# H-Bridge.net
KiCad netlist of a schematic drawn in Altium Designer
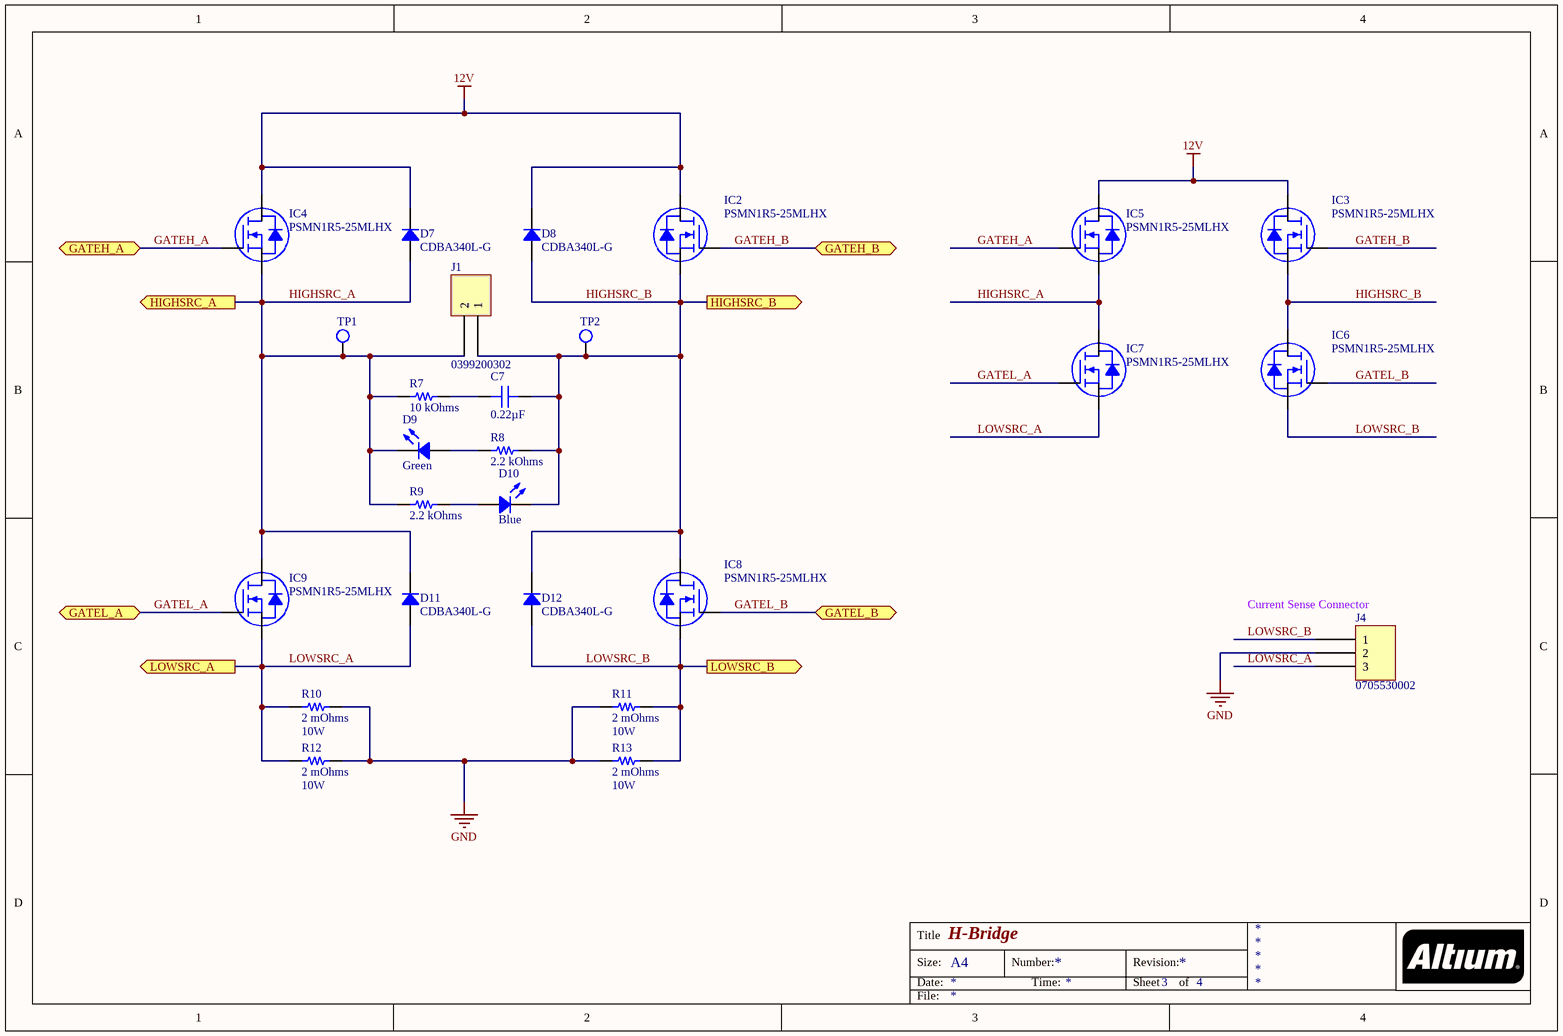
[diagram p0: H-Bridge.SchDoc]

(export (version "E")
  (design (tool "Eeschema 10.0.6"))
  (components
    (comp (ref "C7")
      (value "0.22µF")
      (footprint "CAP 0805_2012")
      (description "CAP CER 0.22UF 50V X7R 0805")
      (fields (field (name "PART NUMBER") "08055C224KAZ2A") (field (name "MANUFACTURER") "AVX Corporation"))
      (libsource (lib "altiumlibrary.com") (part "Capacitor"))
    )
    (comp (ref "D7")
      (value "CDBA340L-G")
      (footprint "DO214AC SMA")
      (description "DIODE SCHOTTKY 40V 3A DO214AC")
      (fields (field (name "MANUFACTURER") "Comchip Technology"))
      (libsource (lib "altiumlibrary.com") (part "Diode"))
    )
    (comp (ref "D8")
      (value "CDBA340L-G")
      (footprint "DO214AC SMA")
      (description "DIODE SCHOTTKY 40V 3A DO214AC")
      (fields (field (name "MANUFACTURER") "Comchip Technology"))
      (libsource (lib "altiumlibrary.com") (part "Diode"))
    )
    (comp (ref "D9")
      (value "Green")
      (footprint "LED 0603_1608 GREEN")
      (description "LED GREEN CLEAR CHIP SMD")
      (fields (field (name "PART NUMBER") "XZMG53W-1") (field (name "MANUFACTURER") "SunLED"))
      (libsource (lib "altiumlibrary.com") (part "LED"))
    )
    (comp (ref "D10")
      (value "Blue")
      (footprint "LED 0603_1608 BLUE")
      (description "LED BLUE CLEAR 2SMD")
      (fields
        (field (name "PART NUMBER") "19-213SUBC/S400-A5/S208-2/TR8")
        (field (name "MANUFACTURER") "Everlight Electronics Co Ltd")
      )
      (libsource (lib "altiumlibrary.com") (part "LED"))
    )
    (comp (ref "D11")
      (value "CDBA340L-G")
      (footprint "DO214AC SMA")
      (description "DIODE SCHOTTKY 40V 3A DO214AC")
      (fields (field (name "MANUFACTURER") "Comchip Technology"))
      (libsource (lib "altiumlibrary.com") (part "Diode"))
    )
    (comp (ref "D12")
      (value "CDBA340L-G")
      (footprint "DO214AC SMA")
      (description "DIODE SCHOTTKY 40V 3A DO214AC")
      (fields (field (name "MANUFACTURER") "Comchip Technology"))
      (libsource (lib "altiumlibrary.com") (part "Diode"))
    )
    (comp (ref "IC2")
      (value "PSMN1R5-25MLHX")
      (footprint "NEXPERIA LFPAK33 SOT1210")
      (description "MOSFET N-CH 25V 150A LFPAK33")
      (fields (field (name "MANUFACTURER") "Nexperia USA Inc."))
      (libsource (lib "") (part "MOSFET SINGLE GDS_1"))
    )
    (comp (ref "IC3")
      (value "PSMN1R5-25MLHX")
      (footprint "NEXPERIA LFPAK33 SOT1210")
      (description "MOSFET N-CH 25V 150A LFPAK33")
      (fields (field (name "MANUFACTURER") "Nexperia USA Inc."))
      (libsource (lib "") (part "MOSFET SINGLE GDS_1"))
    )
    (comp (ref "IC4")
      (value "PSMN1R5-25MLHX")
      (footprint "NEXPERIA LFPAK33 SOT1210")
      (description "MOSFET N-CH 25V 150A LFPAK33")
      (fields (field (name "MANUFACTURER") "Nexperia USA Inc."))
      (libsource (lib "altiumlibrary.com") (part "MOSFET SINGLE GDS"))
    )
    (comp (ref "IC5")
      (value "PSMN1R5-25MLHX")
      (footprint "NEXPERIA LFPAK33 SOT1210")
      (description "MOSFET N-CH 25V 150A LFPAK33")
      (fields (field (name "MANUFACTURER") "Nexperia USA Inc."))
      (libsource (lib "altiumlibrary.com") (part "MOSFET SINGLE GDS"))
    )
    (comp (ref "IC6")
      (value "PSMN1R5-25MLHX")
      (footprint "NEXPERIA LFPAK33 SOT1210")
      (description "MOSFET N-CH 25V 150A LFPAK33")
      (fields (field (name "MANUFACTURER") "Nexperia USA Inc."))
      (libsource (lib "") (part "MOSFET SINGLE GDS_1"))
    )
    (comp (ref "IC7")
      (value "PSMN1R5-25MLHX")
      (footprint "NEXPERIA LFPAK33 SOT1210")
      (description "MOSFET N-CH 25V 150A LFPAK33")
      (fields (field (name "MANUFACTURER") "Nexperia USA Inc."))
      (libsource (lib "altiumlibrary.com") (part "MOSFET SINGLE GDS"))
    )
    (comp (ref "IC8")
      (value "PSMN1R5-25MLHX")
      (footprint "NEXPERIA LFPAK33 SOT1210")
      (description "MOSFET N-CH 25V 150A LFPAK33")
      (fields (field (name "MANUFACTURER") "Nexperia USA Inc."))
      (libsource (lib "") (part "MOSFET SINGLE GDS_1"))
    )
    (comp (ref "IC9")
      (value "PSMN1R5-25MLHX")
      (footprint "NEXPERIA LFPAK33 SOT1210")
      (description "MOSFET N-CH 25V 150A LFPAK33")
      (fields (field (name "MANUFACTURER") "Nexperia USA Inc."))
      (libsource (lib "altiumlibrary.com") (part "MOSFET SINGLE GDS"))
    )
    (comp (ref "J1")
      (value "0399200302")
      (footprint "MOLEX 0399200302")
      (description "TERM BLK 2P SIDE ENTRY 15MM PCB")
      (fields (field (name "MANUFACTURER") "Molex") (field (name "VOLTAGE") "600 V"))
      (libsource (lib "altiumlibrary.com") (part "2 Pin"))
    )
    (comp (ref "J4")
      (value "0705530002")
      (footprint "MOLEX SDA-70553-3PIN")
      (description "CONN HEADER R/A 3POS 2.54MM")
      (fields (field (name "MANUFACTURER") "Molex"))
      (libsource (lib "altiumlibrary.com") (part "3 Pin"))
    )
    (comp (ref "R7")
      (value "10 kOhms")
      (footprint "RES 0805_2012")
      (description "RES SMD 10K OHM 5% 1/2W 0805")
      (fields
        (field (name "PART NUMBER") "ERJ-P06J103V")
        (field (name "MANUFACTURER") "Panasonic Electronic Components")
      )
      (libsource (lib "altiumlibrary.com") (part "Resistor"))
    )
    (comp (ref "R8")
      (value "2.2 kOhms")
      (footprint "RES 0603_1608")
      (description "RES SMD 2.2K OHM 5% 1/4W 0603")
      (fields
        (field (name "PART NUMBER") "ERJ-PA3J222V")
        (field (name "MANUFACTURER") "Panasonic Electronic Components")
      )
      (libsource (lib "altiumlibrary.com") (part "Resistor"))
    )
    (comp (ref "R9")
      (value "2.2 kOhms")
      (footprint "RES 0603_1608")
      (description "RES SMD 2.2K OHM 5% 1/4W 0603")
      (fields
        (field (name "PART NUMBER") "ERJ-PA3J222V")
        (field (name "MANUFACTURER") "Panasonic Electronic Components")
      )
      (libsource (lib "altiumlibrary.com") (part "Resistor"))
    )
    (comp (ref "R10")
      (value "2 mOhms")
      (footprint "VISHAY WSHP2818")
      (description "RES 0.002 OHM 1% 10W 2818")
      (fields
        (field (name "PART NUMBER") "WSHP28182L000FEA")
        (field (name "MANUFACTURER") "Vishay Dale")
        (field (name "POWER (WATTS)") "10W")
      )
      (libsource (lib "altiumlibrary.com") (part "Resistor"))
    )
    (comp (ref "R11")
      (value "2 mOhms")
      (footprint "VISHAY WSHP2818")
      (description "RES 0.002 OHM 1% 10W 2818")
      (fields
        (field (name "PART NUMBER") "WSHP28182L000FEA")
        (field (name "MANUFACTURER") "Vishay Dale")
        (field (name "POWER (WATTS)") "10W")
      )
      (libsource (lib "altiumlibrary.com") (part "Resistor"))
    )
    (comp (ref "R12")
      (value "2 mOhms")
      (footprint "VISHAY WSHP2818")
      (description "RES 0.002 OHM 1% 10W 2818")
      (fields
        (field (name "PART NUMBER") "WSHP28182L000FEA")
        (field (name "MANUFACTURER") "Vishay Dale")
        (field (name "POWER (WATTS)") "10W")
      )
      (libsource (lib "altiumlibrary.com") (part "Resistor"))
    )
    (comp (ref "R13")
      (value "2 mOhms")
      (footprint "VISHAY WSHP2818")
      (description "RES 0.002 OHM 1% 10W 2818")
      (fields
        (field (name "PART NUMBER") "WSHP28182L000FEA")
        (field (name "MANUFACTURER") "Vishay Dale")
        (field (name "POWER (WATTS)") "10W")
      )
      (libsource (lib "altiumlibrary.com") (part "Resistor"))
    )
    (comp (ref "TP1")
      (value "Test Point")
      (footprint "TestPoint-1.5mm")
      (libsource (lib "CelestialUseful") (part "Test Point"))
    )
    (comp (ref "TP2")
      (value "Test Point")
      (footprint "TestPoint-1.5mm")
      (libsource (lib "CelestialUseful") (part "Test Point"))
    )
  )
  (nets
    (net (code "1") (name "/GATEH_A") (class "Default")
      (node (ref "IC4") (pin "G") (pinfunction "G_G") (pintype "passive"))
      (node (ref "IC5") (pin "G") (pinfunction "G_G") (pintype "passive"))
    )
    (net (code "2") (name "/GATEH_B") (class "Default")
      (node (ref "IC2") (pin "G") (pinfunction "G_G") (pintype "passive"))
      (node (ref "IC3") (pin "G") (pinfunction "G_G") (pintype "passive"))
    )
    (net (code "3") (name "/GATEL_A") (class "Default")
      (node (ref "IC7") (pin "G") (pinfunction "G_G") (pintype "passive"))
      (node (ref "IC9") (pin "G") (pinfunction "G_G") (pintype "passive"))
    )
    (net (code "4") (name "/GATEL_B") (class "Default")
      (node (ref "IC6") (pin "G") (pinfunction "G_G") (pintype "passive"))
      (node (ref "IC8") (pin "G") (pinfunction "G_G") (pintype "passive"))
    )
    (net (code "5") (name "/HIGHSRC_A") (class "Default")
      (node (ref "D11") (pin "2") (pinfunction "2_2") (pintype "passive"))
      (node (ref "D7") (pin "1") (pinfunction "1_1") (pintype "passive"))
      (node (ref "D9") (pin "2") (pinfunction "2_2") (pintype "passive"))
      (node (ref "IC4") (pin "S") (pinfunction "S_S") (pintype "passive"))
      (node (ref "IC5") (pin "S") (pinfunction "S_S") (pintype "passive"))
      (node (ref "IC7") (pin "D") (pinfunction "D_D") (pintype "passive"))
      (node (ref "IC9") (pin "D") (pinfunction "D_D") (pintype "passive"))
      (node (ref "J1") (pin "2") (pinfunction "2_2") (pintype "passive"))
      (node (ref "R7") (pin "1") (pinfunction "1_1") (pintype "passive"))
      (node (ref "R9") (pin "1") (pinfunction "1_1") (pintype "passive"))
      (node (ref "TP1") (pin "1") (pinfunction "TP_1") (pintype "passive"))
    )
    (net (code "6") (name "/HIGHSRC_B") (class "Default")
      (node (ref "C7") (pin "2") (pinfunction "2_2") (pintype "passive"))
      (node (ref "D10") (pin "2") (pinfunction "2_2") (pintype "passive"))
      (node (ref "D12") (pin "2") (pinfunction "2_2") (pintype "passive"))
      (node (ref "D8") (pin "1") (pinfunction "1_1") (pintype "passive"))
      (node (ref "IC2") (pin "S") (pinfunction "S_S") (pintype "passive"))
      (node (ref "IC3") (pin "S") (pinfunction "S_S") (pintype "passive"))
      (node (ref "IC6") (pin "D") (pinfunction "D_D") (pintype "passive"))
      (node (ref "IC8") (pin "D") (pinfunction "D_D") (pintype "passive"))
      (node (ref "J1") (pin "1") (pinfunction "1_1") (pintype "passive"))
      (node (ref "R8") (pin "2") (pinfunction "2_2") (pintype "passive"))
      (node (ref "TP2") (pin "1") (pinfunction "TP_1") (pintype "passive"))
    )
    (net (code "7") (name "/LOWSRC_A") (class "Default")
      (node (ref "D11") (pin "1") (pinfunction "1_1") (pintype "passive"))
      (node (ref "IC7") (pin "S") (pinfunction "S_S") (pintype "passive"))
      (node (ref "IC9") (pin "S") (pinfunction "S_S") (pintype "passive"))
      (node (ref "J4") (pin "3") (pinfunction "3_3") (pintype "passive"))
      (node (ref "R10") (pin "1") (pinfunction "1_1") (pintype "passive"))
      (node (ref "R12") (pin "1") (pinfunction "1_1") (pintype "passive"))
    )
    (net (code "8") (name "/LOWSRC_B") (class "Default")
      (node (ref "D12") (pin "1") (pinfunction "1_1") (pintype "passive"))
      (node (ref "IC6") (pin "S") (pinfunction "S_S") (pintype "passive"))
      (node (ref "IC8") (pin "S") (pinfunction "S_S") (pintype "passive"))
      (node (ref "J4") (pin "1") (pinfunction "1_1") (pintype "passive"))
      (node (ref "R11") (pin "2") (pinfunction "2_2") (pintype "passive"))
      (node (ref "R13") (pin "2") (pinfunction "2_2") (pintype "passive"))
    )
    (net (code "9") (name "12V") (class "Default")
      (node (ref "D7") (pin "2") (pinfunction "2_2") (pintype "passive"))
      (node (ref "D8") (pin "2") (pinfunction "2_2") (pintype "passive"))
      (node (ref "IC2") (pin "D") (pinfunction "D_D") (pintype "passive"))
      (node (ref "IC3") (pin "D") (pinfunction "D_D") (pintype "passive"))
      (node (ref "IC4") (pin "D") (pinfunction "D_D") (pintype "passive"))
      (node (ref "IC5") (pin "D") (pinfunction "D_D") (pintype "passive"))
    )
    (net (code "10") (name "GND") (class "Default")
      (node (ref "J4") (pin "2") (pinfunction "2_2") (pintype "passive"))
      (node (ref "R10") (pin "2") (pinfunction "2_2") (pintype "passive"))
      (node (ref "R11") (pin "1") (pinfunction "1_1") (pintype "passive"))
      (node (ref "R12") (pin "2") (pinfunction "2_2") (pintype "passive"))
      (node (ref "R13") (pin "1") (pinfunction "1_1") (pintype "passive"))
    )
    (net (code "11") (name "Net-(C7-Pad1)") (class "Default")
      (node (ref "C7") (pin "1") (pinfunction "1_1") (pintype "passive"))
      (node (ref "R7") (pin "2") (pinfunction "2_2") (pintype "passive"))
    )
    (net (code "12") (name "Net-(D9-Pad1)") (class "Default")
      (node (ref "D9") (pin "1") (pinfunction "1_1") (pintype "passive"))
      (node (ref "R8") (pin "1") (pinfunction "1_1") (pintype "passive"))
    )
    (net (code "13") (name "Net-(D10-Pad1)") (class "Default")
      (node (ref "D10") (pin "1") (pinfunction "1_1") (pintype "passive"))
      (node (ref "R9") (pin "2") (pinfunction "2_2") (pintype "passive"))
    )
  )
)
